# Differential_driver.net
KiCad netlist of a schematic drawn in Altium Designer
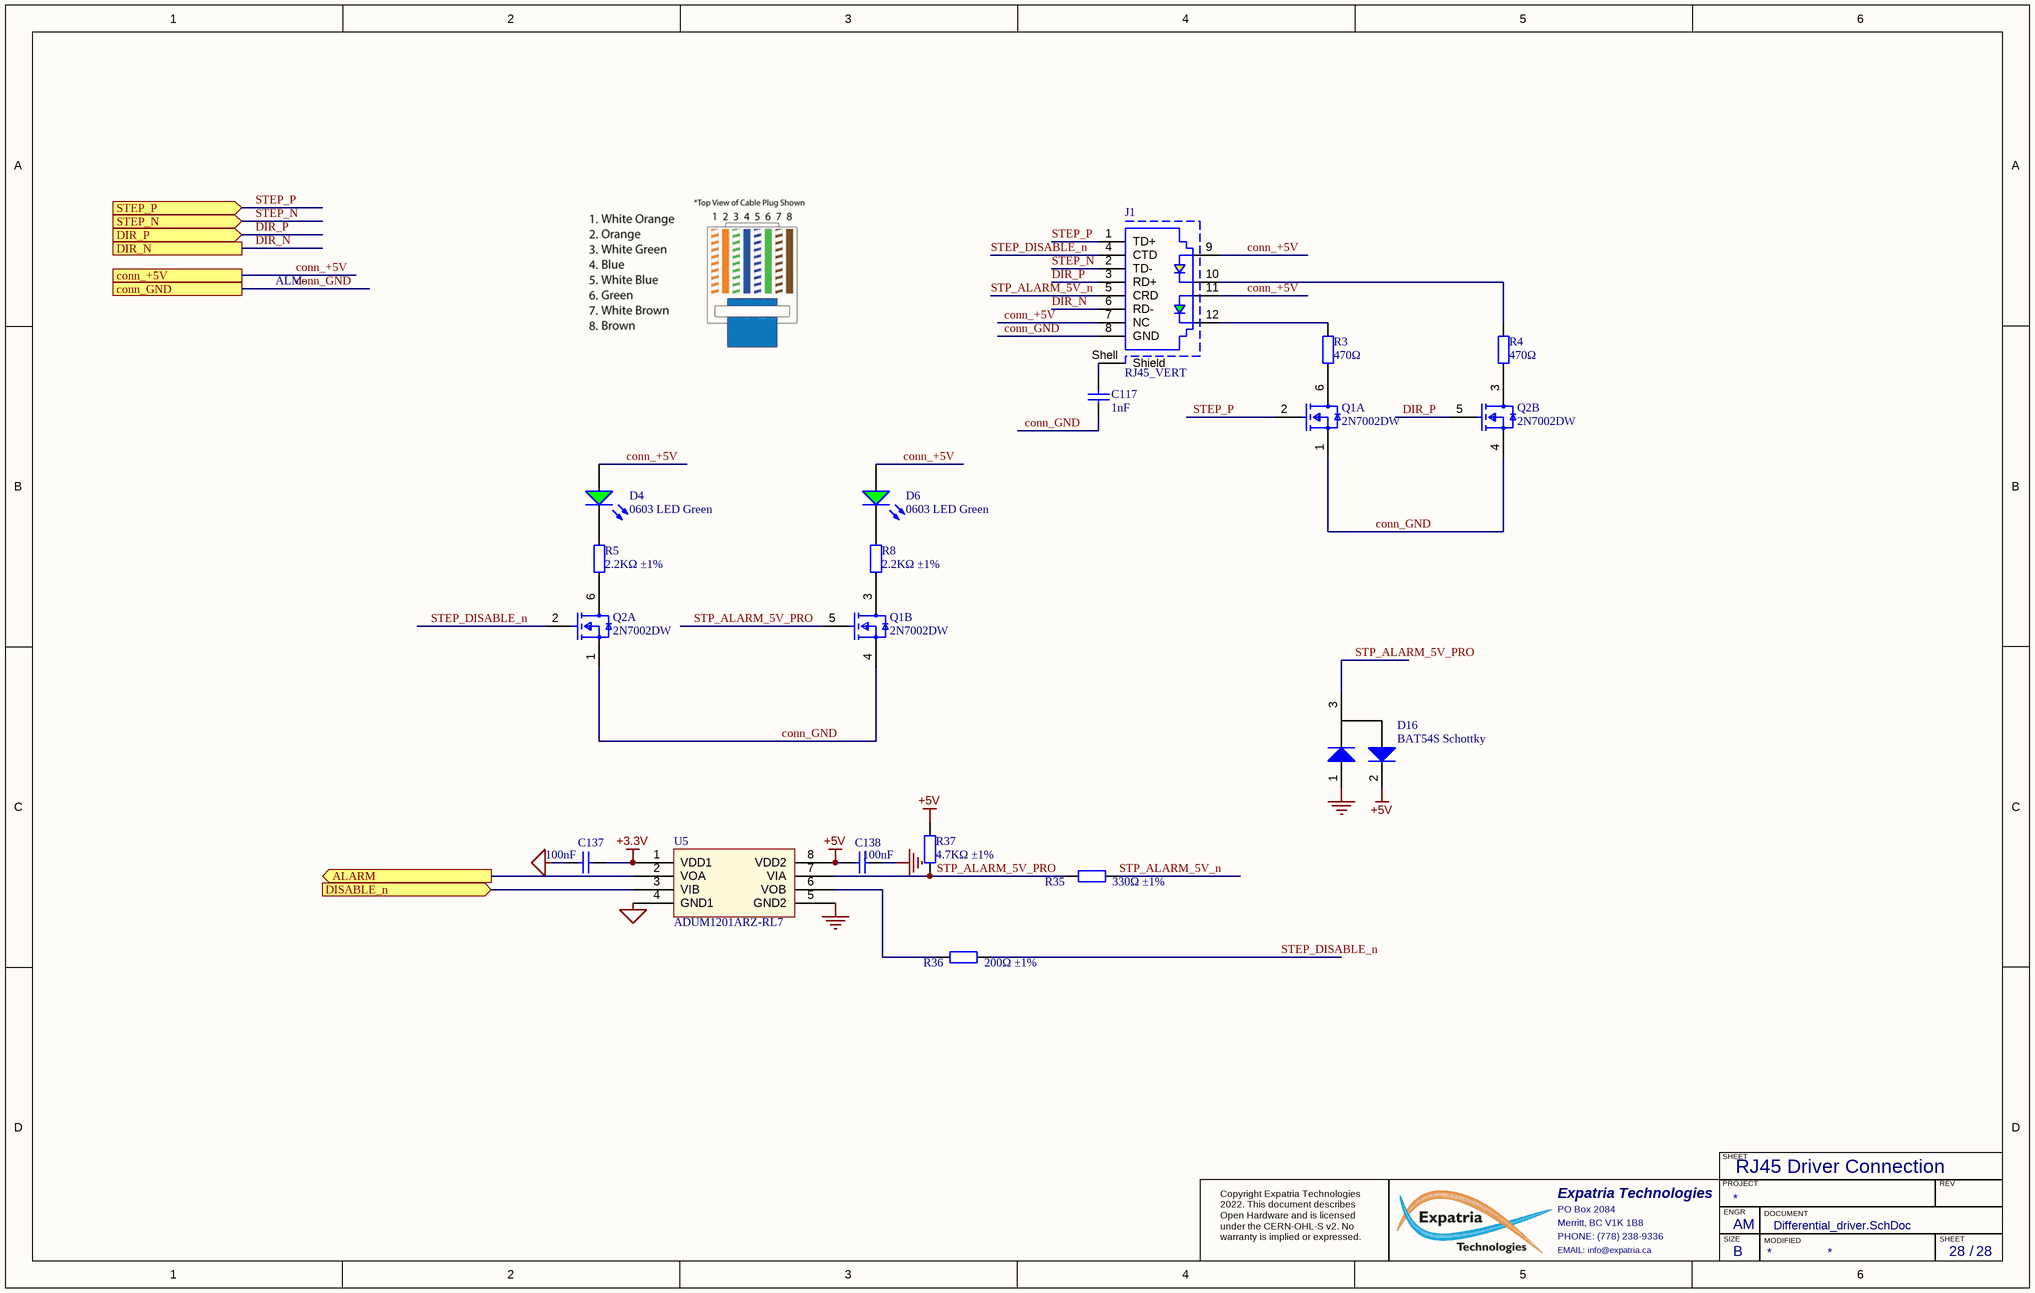
[diagram p0: Differential_driver.SchDoc]

(export (version "E")
  (design (tool "Eeschema 10.0.6"))
  (components
    (comp (ref "C117")
      (value "1nF")
      (footprint "0603_C")
      (description "Chip capacitors")
      (fields
        (field (name "MANUFACTURER") "Samsung Electro-Mechanics")
        (field (name "PARTNUMBER") "CL10B102KB8NNNC")
      )
      (libsource (lib "Cap") (part "0603 1nF (102) 10% 50V"))
    )
    (comp (ref "C137")
      (value "100nF")
      (footprint "0402_C")
      (description "Chip capacitors")
      (fields
        (field (name "MANUFACTURER") "Samsung Electro-Mechanics")
        (field (name "PARTNUMBER") "CL05B104KO5NNNC")
      )
      (libsource (lib "Cap") (part "0402 100nF (104) 10% 16V"))
    )
    (comp (ref "C138")
      (value "100nF")
      (footprint "0402_C")
      (description "Chip capacitors")
      (fields
        (field (name "MANUFACTURER") "Samsung Electro-Mechanics")
        (field (name "PARTNUMBER") "CL05B104KO5NNNC")
      )
      (libsource (lib "Cap") (part "0402 100nF (104) 10% 16V"))
    )
    (comp (ref "D4")
      (value "0603 LED Green")
      (footprint "0603_LED_S1 - GREEN")
      (fields
        (field (name "MANUFACTURER PART NUMBER") "19-217/GHC-YR1S2/3T")
        (field (name "MANUFACTURER") "Everlight Elec")
      )
      (libsource (lib "Sienci_Labs") (part "19-217/GHC-YR1S2/3T"))
    )
    (comp (ref "D6")
      (value "0603 LED Green")
      (footprint "0603_LED_S1 - GREEN")
      (fields
        (field (name "MANUFACTURER PART NUMBER") "19-217/GHC-YR1S2/3T")
        (field (name "MANUFACTURER") "Everlight Elec")
      )
      (libsource (lib "Sienci_Labs") (part "19-217/GHC-YR1S2/3T"))
    )
    (comp (ref "D16")
      (value "BAT54S Schottky")
      (footprint "SOT-23(SOT-23-3)")
      (description "30V Dual 200mA 800mV@100mA SOT-23 Schottky Barrier Diodes (SBD) ROHS")
      (libsource (lib "Diode") (part "SOT-23 BAT54S"))
    )
    (comp (ref "J1")
      (value "RJ45_VERT")
      (footprint "74990101210")
      (description "Telecom and Datacom Connector, 8 Contact(s), Female, Straight, Solder Terminal")
      (libsource (lib "Cambridge Mobile Telematics, Inc") (part "74990101210"))
    )
    (comp (ref "Q1")
      (value "2N7002DW")
      (footprint "FP-PG-SOT363-6-MFG")
      (description "60V 300mA 1.9Ω@10V,0.3A 300mW 2.5V 2 N-Channel SOT-363 MOSFETs ROHS")
      (libsource (lib "Altium Content Vault") (part "226acf62e6c56029797c43a6c48a86b"))
    )
    (comp (ref "Q2")
      (value "2N7002DW")
      (footprint "FP-PG-SOT363-6-MFG")
      (description "60V 300mA 1.9Ω@10V,0.3A 300mW 2.5V 2 N-Channel SOT-363 MOSFETs ROHS")
      (libsource (lib "Altium Content Vault") (part "226acf62e6c56029797c43a6c48a86b"))
    )
    (comp (ref "R3")
      (value "470Ω ±1%")
      (footprint "0402_R")
      (description "Chip resistor")
      (fields
        (field (name "TOLERANCE") "1%")
        (field (name "POWER") "1/16W")
        (field (name "RESISTANCE") "470Ω")
      )
      (libsource (lib "RES") (part "0402 470R (4700) 1%"))
    )
    (comp (ref "R4")
      (value "470Ω ±1%")
      (footprint "0402_R")
      (description "Chip resistor")
      (fields
        (field (name "TOLERANCE") "1%")
        (field (name "POWER") "1/16W")
        (field (name "RESISTANCE") "470Ω")
      )
      (libsource (lib "RES") (part "0402 470R (4700) 1%"))
    )
    (comp (ref "R5")
      (value "2.2KΩ ±1%")
      (footprint "0402_R")
      (description "Chip resistor")
      (fields (field (name "MANUFACTURER") "Uniroyal Elec") (field (name "POWER") "1/16W"))
      (libsource (lib "RES") (part "0402 2.2K (2201) 1%"))
    )
    (comp (ref "R8")
      (value "2.2KΩ ±1%")
      (footprint "0402_R")
      (description "Chip resistor")
      (fields (field (name "MANUFACTURER") "Uniroyal Elec") (field (name "POWER") "1/16W"))
      (libsource (lib "RES") (part "0402 2.2K (2201) 1%"))
    )
    (comp (ref "R35")
      (value "330Ω ±1%")
      (footprint "0402_R")
      (description "Chip resistor")
      (fields (field (name "MANUFACTURER") "Uniroyal Elec") (field (name "PARTNUMBER") "0402WGF3300TCE"))
      (libsource (lib "RES") (part "0402 330R (3300) 1%"))
    )
    (comp (ref "R36")
      (value "200Ω ±1%")
      (footprint "0402_R")
      (description "Chip resistor")
      (fields (field (name "MANUFACTURER") "Uniroyal Elec") (field (name "PARTNUMBER") "0402WGF2000TCE"))
      (libsource (lib "RES") (part "0402 200R (2000) 1%"))
    )
    (comp (ref "R37")
      (value "4.7KΩ ±1%")
      (footprint "0402_R")
      (description "Chip resistor")
      (fields (field (name "MANUFACTURER") "Uniroyal Elec") (field (name "PARTNUMBER") "0402WGF4701TCE"))
      (libsource (lib "RES") (part "0402 4.7K (4701) 1%"))
    )
    (comp (ref "U5")
      (value "ADUM1201ARZ-RL7")
      (footprint "SOIC-8_150mil")
      (description "Dual Channel Isolator")
      (libsource (lib "IC") (part "ADUM1201ARZ-RL7_[C9669]"))
    )
  )
  (nets
    (net (code "1") (name "+3.3V") (class "Default")
      (node (ref "C137") (pin "1") (pinfunction "1_1") (pintype "passive"))
      (node (ref "U5") (pin "1") (pinfunction "VDD1_1") (pintype "passive"))
    )
    (net (code "2") (name "+5V") (class "Default")
      (node (ref "C138") (pin "2") (pinfunction "2_2") (pintype "passive"))
      (node (ref "D16") (pin "2") (pinfunction "A_2") (pintype "passive"))
      (node (ref "R37") (pin "2") (pinfunction "2_2") (pintype "passive"))
      (node (ref "U5") (pin "8") (pinfunction "VDD2_8") (pintype "passive"))
    )
    (net (code "3") (name "/ALARM") (class "Default")
      (node (ref "U5") (pin "2") (pinfunction "VOA_2") (pintype "passive"))
    )
    (net (code "4") (name "/DIR_N") (class "Default")
      (node (ref "J1") (pin "6") (pinfunction "RD-_6") (pintype "passive"))
    )
    (net (code "5") (name "/DIR_P") (class "Default")
      (node (ref "J1") (pin "3") (pinfunction "RD+_3") (pintype "passive"))
      (node (ref "Q2") (pin "5") (pinfunction "G2_5") (pintype "passive"))
    )
    (net (code "6") (name "/DISABLE_n") (class "Default")
      (node (ref "U5") (pin "3") (pinfunction "VIB_3") (pintype "passive"))
    )
    (net (code "7") (name "/STEP_DISABLE_n") (class "Default")
      (node (ref "J1") (pin "4") (pinfunction "CTD_4") (pintype "passive"))
      (node (ref "Q2") (pin "2") (pinfunction "G1_2") (pintype "passive"))
      (node (ref "R36") (pin "2") (pinfunction "2_2") (pintype "passive"))
    )
    (net (code "8") (name "/STEP_N") (class "Default")
      (node (ref "J1") (pin "2") (pinfunction "TD-_2") (pintype "passive"))
    )
    (net (code "9") (name "/STEP_P") (class "Default")
      (node (ref "J1") (pin "1") (pinfunction "TD+_1") (pintype "passive"))
      (node (ref "Q1") (pin "2") (pinfunction "G1_2") (pintype "passive"))
    )
    (net (code "10") (name "/STP_ALARM_5V_PRO") (class "Default")
      (node (ref "D16") (pin "3") (pinfunction "K_3") (pintype "passive"))
      (node (ref "Q1") (pin "5") (pinfunction "G2_5") (pintype "passive"))
      (node (ref "R35") (pin "1") (pinfunction "1_1") (pintype "passive"))
      (node (ref "R37") (pin "1") (pinfunction "1_1") (pintype "passive"))
      (node (ref "U5") (pin "7") (pinfunction "VIA_7") (pintype "passive"))
    )
    (net (code "11") (name "/STP_ALARM_5V_n") (class "Default")
      (node (ref "J1") (pin "5") (pinfunction "CRD_5") (pintype "passive"))
      (node (ref "R35") (pin "2") (pinfunction "2_2") (pintype "passive"))
    )
    (net (code "12") (name "/conn_+5V") (class "Default")
      (node (ref "D4") (pin "A") (pinfunction "A_A") (pintype "passive"))
      (node (ref "D6") (pin "A") (pinfunction "A_A") (pintype "passive"))
      (node (ref "J1") (pin "11") (pinfunction "11_11") (pintype "passive"))
      (node (ref "J1") (pin "7") (pinfunction "NC_7") (pintype "passive"))
      (node (ref "J1") (pin "9") (pinfunction "9_9") (pintype "passive"))
    )
    (net (code "13") (name "/conn_GND") (class "Default")
      (node (ref "C117") (pin "1") (pinfunction "1_1") (pintype "passive"))
      (node (ref "J1") (pin "8") (pinfunction "GND_8") (pintype "passive"))
      (node (ref "Q1") (pin "1") (pinfunction "S1_1") (pintype "passive"))
      (node (ref "Q1") (pin "4") (pinfunction "S2_4") (pintype "passive"))
      (node (ref "Q2") (pin "1") (pinfunction "S1_1") (pintype "passive"))
      (node (ref "Q2") (pin "4") (pinfunction "S2_4") (pintype "passive"))
    )
    (net (code "14") (name "GND") (class "Default")
      (node (ref "C138") (pin "1") (pinfunction "1_1") (pintype "passive"))
      (node (ref "D16") (pin "1") (pinfunction "A_1") (pintype "passive"))
      (node (ref "U5") (pin "5") (pinfunction "GND2_5") (pintype "passive"))
    )
    (net (code "15") (name "MCU_GND") (class "Default")
      (node (ref "C137") (pin "2") (pinfunction "2_2") (pintype "passive"))
      (node (ref "U5") (pin "4") (pinfunction "GND1_4") (pintype "passive"))
    )
    (net (code "16") (name "Net-(D4-PadK)") (class "Default")
      (node (ref "D4") (pin "K") (pinfunction "K_K") (pintype "passive"))
      (node (ref "R5") (pin "2") (pinfunction "2_2") (pintype "passive"))
    )
    (net (code "17") (name "Net-(D6-PadK)") (class "Default")
      (node (ref "D6") (pin "K") (pinfunction "K_K") (pintype "passive"))
      (node (ref "R8") (pin "2") (pinfunction "2_2") (pintype "passive"))
    )
    (net (code "18") (name "Net-(J1-Pad10)") (class "Default")
      (node (ref "J1") (pin "10") (pinfunction "10_10") (pintype "passive"))
      (node (ref "R4") (pin "2") (pinfunction "2_2") (pintype "passive"))
    )
    (net (code "19") (name "Net-(J1-Pad12)") (class "Default")
      (node (ref "J1") (pin "12") (pinfunction "12_12") (pintype "passive"))
      (node (ref "R3") (pin "2") (pinfunction "2_2") (pintype "passive"))
    )
    (net (code "20") (name "Net-(J1-Shield)") (class "Default")
      (node (ref "C117") (pin "2") (pinfunction "2_2") (pintype "passive"))
      (node (ref "J1") (pin "Shell") (pinfunction "Shield_Shell") (pintype "passive"))
    )
    (net (code "21") (name "Net-(Q1A-D1)") (class "Default")
      (node (ref "Q1") (pin "6") (pinfunction "D1_6") (pintype "passive"))
      (node (ref "R3") (pin "1") (pinfunction "1_1") (pintype "passive"))
    )
    (net (code "22") (name "Net-(Q1B-D2)") (class "Default")
      (node (ref "Q1") (pin "3") (pinfunction "D2_3") (pintype "passive"))
      (node (ref "R8") (pin "1") (pinfunction "1_1") (pintype "passive"))
    )
    (net (code "23") (name "Net-(Q2A-D1)") (class "Default")
      (node (ref "Q2") (pin "6") (pinfunction "D1_6") (pintype "passive"))
      (node (ref "R5") (pin "1") (pinfunction "1_1") (pintype "passive"))
    )
    (net (code "24") (name "Net-(Q2B-D2)") (class "Default")
      (node (ref "Q2") (pin "3") (pinfunction "D2_3") (pintype "passive"))
      (node (ref "R4") (pin "1") (pinfunction "1_1") (pintype "passive"))
    )
    (net (code "25") (name "Net-(U5-VOB)") (class "Default")
      (node (ref "R36") (pin "1") (pinfunction "1_1") (pintype "passive"))
      (node (ref "U5") (pin "6") (pinfunction "VOB_6") (pintype "passive"))
    )
  )
)
